# Capteur.net
KiCad netlist of a schematic drawn in Altium Designer
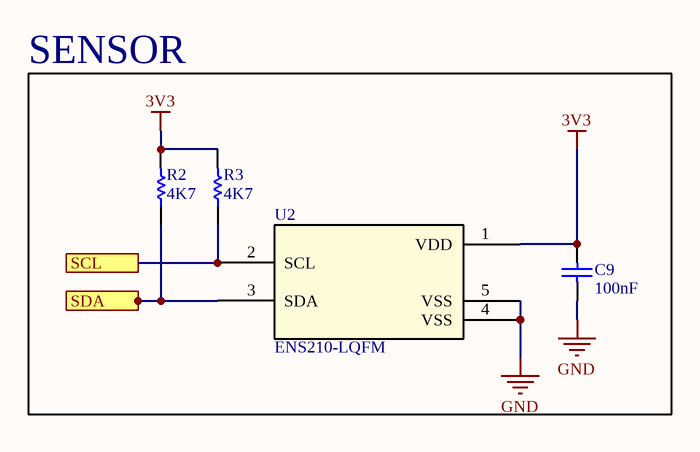
[diagram p0: Capteur.SchDoc]

(export (version "E")
  (design (tool "Eeschema 10.0.6"))
  (components
    (comp (ref "C9")
      (value "100nF")
      (footprint "CAP_0402L")
      (description "CAP CER 100nF 16V X7R 10% 0402")
      (fields (field (name "TOLERANCE") "10%"))
      (libsource (lib "PCB_training_Project") (part "CAP CER 100nF"))
    )
    (comp (ref "R2")
      (value "4K7")
      (footprint "RES_0402N")
      (description "RES SMD 4.7K OHM 1% 1/16W 0402")
      (fields (field (name "TOLERANCE") "1%"))
      (libsource (lib "PCB_training_Project") (part "Res_4K7"))
    )
    (comp (ref "R3")
      (value "4K7")
      (footprint "RES_0402N")
      (description "RES SMD 4.7K OHM 1% 1/16W 0402")
      (fields (field (name "TOLERANCE") "1%"))
      (libsource (lib "PCB_training_Project") (part "Res_4K7"))
    )
    (comp (ref "U2")
      (value "ENS210-LQFM")
      (footprint "SON-04-ENS210_2X2_AMS")
      (description "Description")
      (fields (field (name "COPYRIGHT") "Copyright (C) 2025 Ultra Librarian. All rights reserved."))
      (libsource (lib "PCB_training_Project") (part "ENS210-LQFM"))
    )
  )
  (nets
    (net (code "1") (name "/SCL") (class "Default")
      (node (ref "R3") (pin "1") (pinfunction "1_1") (pintype "passive"))
      (node (ref "U2") (pin "2") (pinfunction "SCL_2") (pintype "passive"))
    )
    (net (code "2") (name "/SDA") (class "Default")
      (node (ref "R2") (pin "1") (pinfunction "1_1") (pintype "passive"))
      (node (ref "U2") (pin "3") (pinfunction "SDA_3") (pintype "passive"))
    )
    (net (code "3") (name "3V3") (class "Default")
      (node (ref "C9") (pin "2") (pinfunction "2_2") (pintype "passive"))
      (node (ref "R2") (pin "2") (pinfunction "2_2") (pintype "passive"))
      (node (ref "R3") (pin "2") (pinfunction "2_2") (pintype "passive"))
      (node (ref "U2") (pin "1") (pinfunction "VDD_1") (pintype "power_in"))
    )
    (net (code "4") (name "GND") (class "Default")
      (node (ref "C9") (pin "1") (pinfunction "1_1") (pintype "passive"))
      (node (ref "U2") (pin "4") (pinfunction "VSS_4") (pintype "power_in"))
      (node (ref "U2") (pin "5") (pinfunction "VSS_5") (pintype "power_in"))
    )
  )
)
